# NinjaPCB_ver2-180115.net
KiCad netlist of a schematic drawn in EAGLE
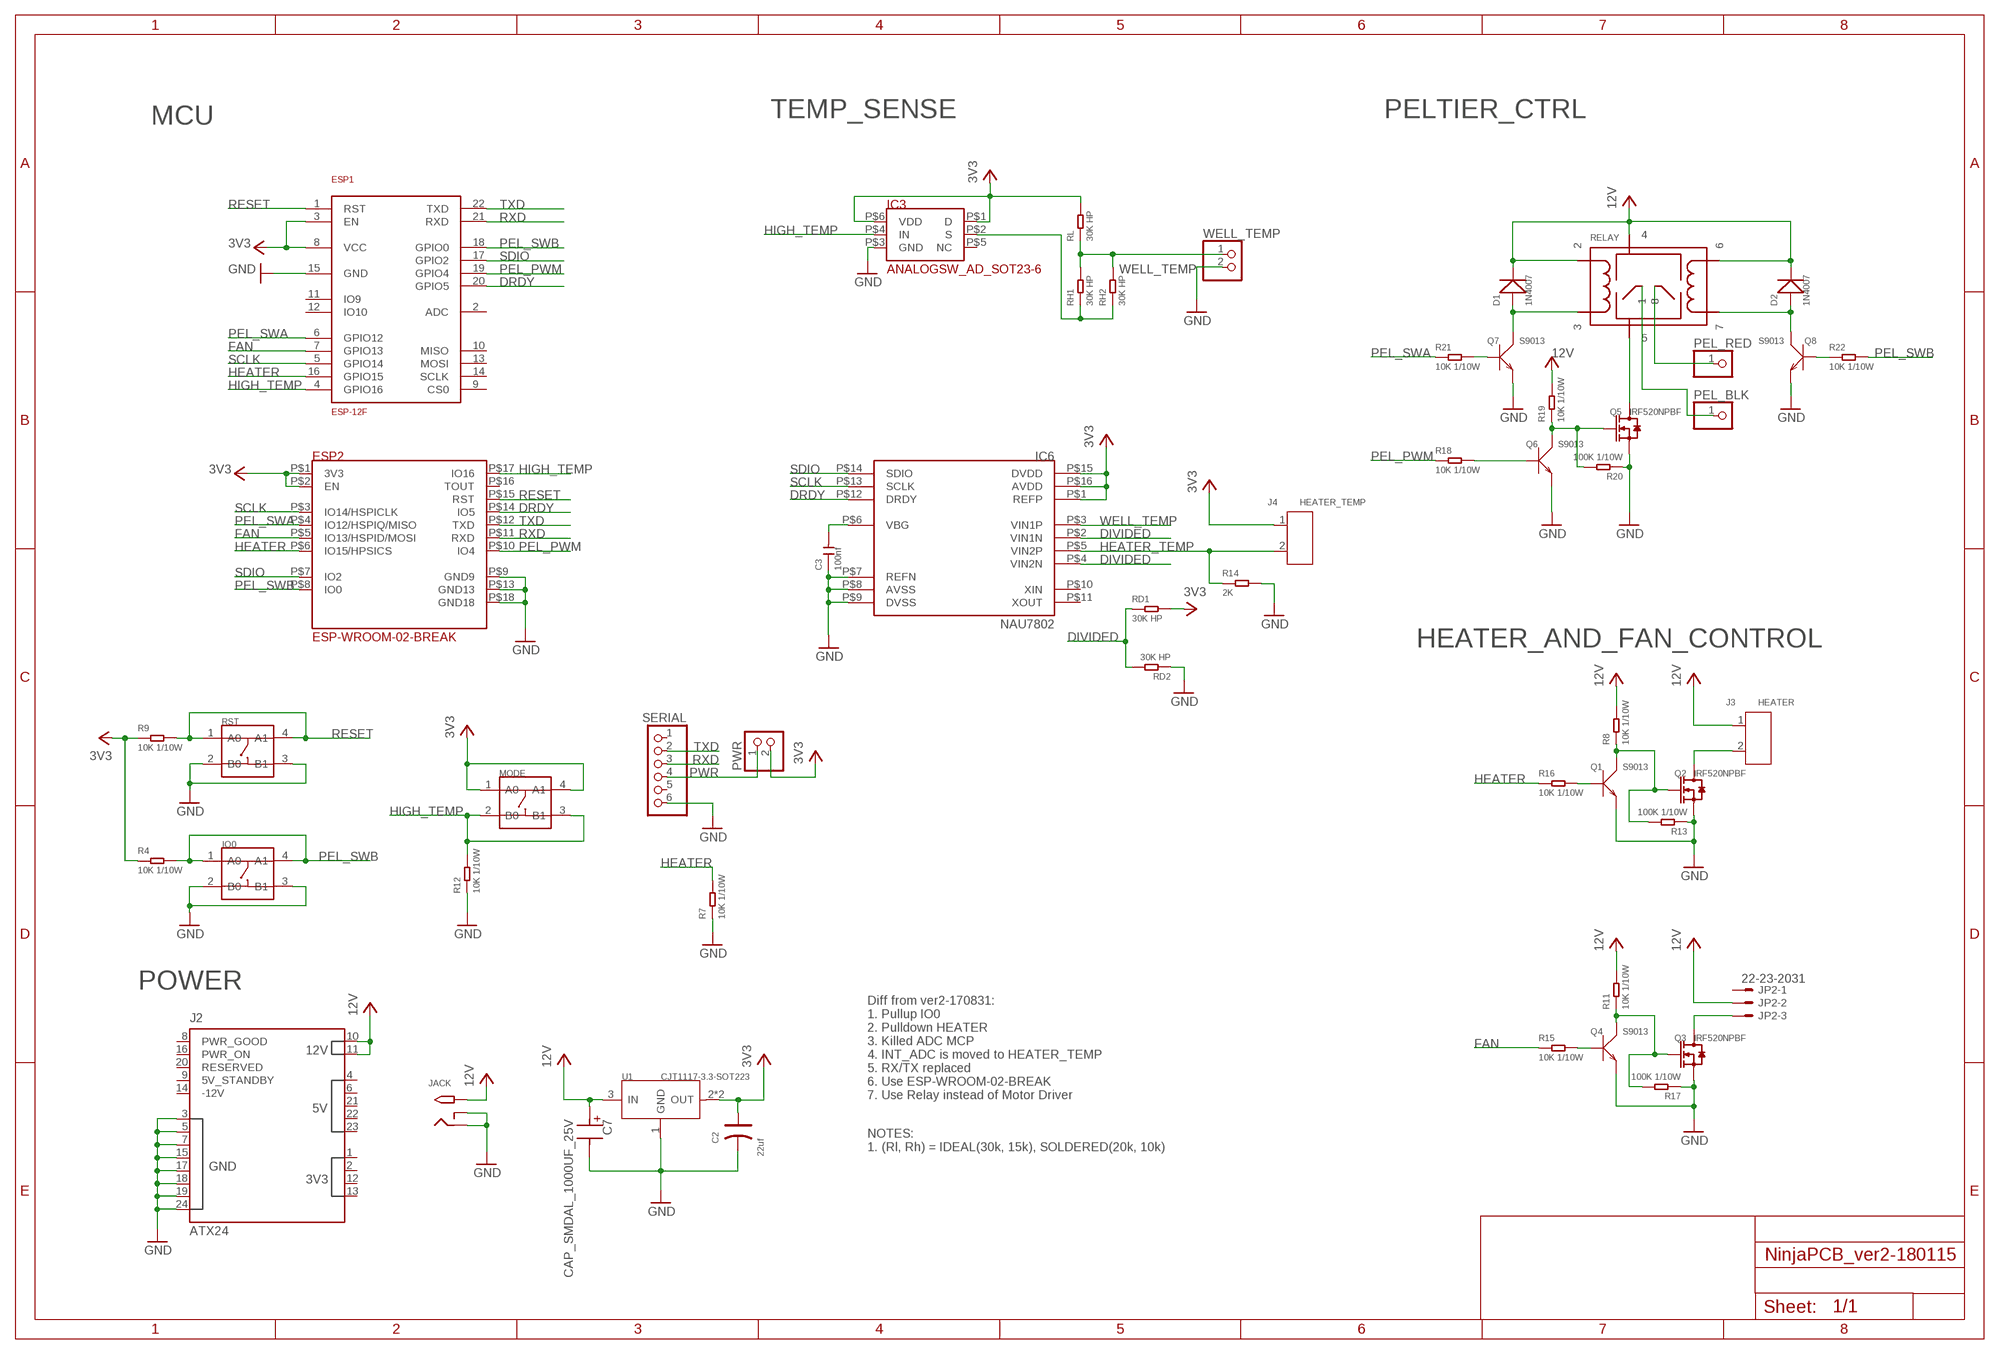
[diagram p0: schematic, sheet 1]

(export (version "E")
  (design (tool "Eeschema 10.0.6"))
  (components
    (comp (ref "C2")
      (value "22uf")
      (footprint "eagle-import:AVX-B")
      (fields (field (name "MPN") "TAJB226*016#NJ"))
      (libsource (lib "eagle-import") (part "TANTALUM-SMD-22UF-16V(AVX-B)"))
    )
    (comp (ref "C3")
      (value "100nf")
      (footprint "eagle-import:C0603")
      (fields (field (name "MPN") "CC0603KRX7R9BB104"))
      (libsource (lib "eagle-import") (part "CERAMIC-100NF-50V-10%-X7R(0603)"))
    )
    (comp (ref "C7")
      (value "CAP_SMDAL_1000UF_25V")
      (footprint "eagle-import:CAP_SMD_AL_D125")
      (libsource (lib "eagle-import") (part "CAP_SMDAL_1000UF_25V"))
    )
    (comp (ref "D1")
      (value "1N4007")
      (footprint "eagle-import:DO-214AC")
      (libsource (lib "eagle-import") (part "DIODE-GEN-PURPOSE-1KV-1A(DO-214AC)"))
    )
    (comp (ref "D2")
      (value "1N4007")
      (footprint "eagle-import:DO-214AC")
      (libsource (lib "eagle-import") (part "DIODE-GEN-PURPOSE-1KV-1A(DO-214AC)"))
    )
    (comp (ref "ESP1")
      (value "ESP-12F")
      (footprint "eagle-import:ESP-12F")
      (libsource (lib "eagle-import") (part "ESP-12F"))
    )
    (comp (ref "ESP2")
      (value "ESP-WROOM-02-BREAK")
      (footprint "eagle-import:ESP-WROOM-02-BREAK")
      (libsource (lib "eagle-import") (part "ESP-WROOM-02-BREAK"))
    )
    (comp (ref "IC3")
      (value "ANALOGSW_AD_SOT23-6")
      (footprint "eagle-import:SOT-23-6")
      (libsource (lib "eagle-import") (part "ANALOGSW_AD_SOT23-6"))
    )
    (comp (ref "IC6")
      (value "NAU7802")
      (footprint "eagle-import:SOP-16")
      (libsource (lib "eagle-import") (part "NAU7802"))
    )
    (comp (ref "IO0")
      (value "DIP-SWITCH-TACTILE-SPST-NO/TS-1109(4P-D6.0MM)'TS-1109'")
      (footprint "eagle-import:SW4-6.0X6.0X5.0MM")
      (libsource (lib "eagle-import") (part "DIP-SWITCH-TACTILE-SPST-NO/TS-1109(4P-D6.0MM)'TS-1109'"))
    )
    (comp (ref "J2")
      (value "ATX24")
      (footprint "eagle-import:ATX24")
      (libsource (lib "eagle-import") (part "ATX24"))
    )
    (comp (ref "J3")
      (value "HEATER")
      (footprint "eagle-import:H2-3.5-7.0X7.0MM")
      (libsource (lib "eagle-import") (part "SCREW-TERMINAL-GREEN(2P-3.5)"))
    )
    (comp (ref "J4")
      (value "HEATER_TEMP")
      (footprint "eagle-import:H2-3.5-7.0X7.0MM")
      (libsource (lib "eagle-import") (part "SCREW-TERMINAL-GREEN(2P-3.5)"))
    )
    (comp (ref "JACK")
      (value "2.1MMJACKTHM")
      (footprint "eagle-import:PJ-102A")
      (libsource (lib "eagle-import") (part "2.1MMJACKTHM"))
    )
    (comp (ref "JP2")
      (value "22-23-2031")
      (footprint "eagle-import:22-23-2031")
      (fields (field (name "MF") "MOLEX"))
      (libsource (lib "eagle-import") (part "22-23-2031"))
    )
    (comp (ref "MODE")
      (value "DIP-SWITCH-TACTILE-SPST-NO/TS-1109(4P-D6.0MM)'TS-1109'")
      (footprint "eagle-import:SW4-6.0X6.0X5.0MM")
      (libsource (lib "eagle-import") (part "DIP-SWITCH-TACTILE-SPST-NO/TS-1109(4P-D6.0MM)'TS-1109'"))
    )
    (comp (ref "PEL_BLK")
      (value "PINHD-1X1L")
      (footprint "eagle-import:1X01LONG")
      (libsource (lib "eagle-import") (part "PINHD-1X1L"))
    )
    (comp (ref "PEL_RED")
      (value "PINHD-1X1L")
      (footprint "eagle-import:1X01LONG")
      (libsource (lib "eagle-import") (part "PINHD-1X1L"))
    )
    (comp (ref "PWR")
      (value "PINHD-1X2")
      (footprint "eagle-import:1X02")
      (libsource (lib "eagle-import") (part "PINHD-1X2"))
    )
    (comp (ref "Q1")
      (value "S9013")
      (footprint "eagle-import:SOT-23")
      (libsource (lib "eagle-import") (part "SMD-TRANSISTORS-NPN-25V-500MA-S9013(SOT-23)"))
    )
    (comp (ref "Q2")
      (value "IRF520NPBF")
      (footprint "eagle-import:TO-220")
      (libsource (lib "eagle-import") (part "DIP-MOSFET-N-CH-100V-9.7A-IRF520NPBF(TO-220AB)CORRECT"))
    )
    (comp (ref "Q3")
      (value "IRF520NPBF")
      (footprint "eagle-import:TO-220")
      (libsource (lib "eagle-import") (part "DIP-MOSFET-N-CH-100V-9.7A-IRF520NPBF(TO-220AB)CORRECT"))
    )
    (comp (ref "Q4")
      (value "S9013")
      (footprint "eagle-import:SOT-23")
      (libsource (lib "eagle-import") (part "SMD-TRANSISTORS-NPN-25V-500MA-S9013(SOT-23)"))
    )
    (comp (ref "Q5")
      (value "IRF520NPBF")
      (footprint "eagle-import:TO-220")
      (libsource (lib "eagle-import") (part "DIP-MOSFET-N-CH-100V-9.7A-IRF520NPBF(TO-220AB)CORRECT"))
    )
    (comp (ref "Q6")
      (value "S9013")
      (footprint "eagle-import:SOT-23")
      (libsource (lib "eagle-import") (part "SMD-TRANSISTORS-NPN-25V-500MA-S9013(SOT-23)"))
    )
    (comp (ref "Q7")
      (value "S9013")
      (footprint "eagle-import:SOT-23")
      (libsource (lib "eagle-import") (part "SMD-TRANSISTORS-NPN-25V-500MA-S9013(SOT-23)"))
    )
    (comp (ref "Q8")
      (value "S9013")
      (footprint "eagle-import:SOT-23")
      (libsource (lib "eagle-import") (part "SMD-TRANSISTORS-NPN-25V-500MA-S9013(SOT-23)"))
    )
    (comp (ref "R4")
      (value "10K 1/10W")
      (footprint "eagle-import:R0603")
      (fields (field (name "MPN") "RC0603JR-0710KL"))
      (libsource (lib "eagle-import") (part "SMD-RES-10K-5%-1/10W(0603)"))
    )
    (comp (ref "R7")
      (value "10K 1/10W")
      (footprint "eagle-import:R0603")
      (fields (field (name "MPN") "RC0603JR-0710KL"))
      (libsource (lib "eagle-import") (part "SMD-RES-10K-5%-1/10W(0603)"))
    )
    (comp (ref "R8")
      (value "10K 1/10W")
      (footprint "eagle-import:R0603")
      (fields (field (name "MPN") "RC0603JR-0710KL"))
      (libsource (lib "eagle-import") (part "SMD-RES-10K-5%-1/10W(0603)"))
    )
    (comp (ref "R9")
      (value "10K 1/10W")
      (footprint "eagle-import:R0603")
      (fields (field (name "MPN") "RC0603JR-0710KL"))
      (libsource (lib "eagle-import") (part "SMD-RES-10K-5%-1/10W(0603)"))
    )
    (comp (ref "R11")
      (value "10K 1/10W")
      (footprint "eagle-import:R0603")
      (fields (field (name "MPN") "RC0603JR-0710KL"))
      (libsource (lib "eagle-import") (part "SMD-RES-10K-5%-1/10W(0603)"))
    )
    (comp (ref "R12")
      (value "10K 1/10W")
      (footprint "eagle-import:R0603")
      (fields (field (name "MPN") "RC0603JR-0710KL"))
      (libsource (lib "eagle-import") (part "SMD-RES-10K-5%-1/10W(0603)"))
    )
    (comp (ref "R13")
      (value "100K 1/10W")
      (footprint "eagle-import:R0603")
      (fields (field (name "MPN") "RC0603JR-07100KL"))
      (libsource (lib "eagle-import") (part "SMD-RES-100K-5%-1/10W(0603)"))
    )
    (comp (ref "R14")
      (value "2K")
      (footprint "eagle-import:R0603")
      (fields (field (name "MPN") "RC0603FR-072KL"))
      (libsource (lib "eagle-import") (part "SMD-RES-2K-1%-1/10W(0603)"))
    )
    (comp (ref "R15")
      (value "10K 1/10W")
      (footprint "eagle-import:R0603")
      (fields (field (name "MPN") "RC0603JR-0710KL"))
      (libsource (lib "eagle-import") (part "SMD-RES-10K-5%-1/10W(0603)"))
    )
    (comp (ref "R16")
      (value "10K 1/10W")
      (footprint "eagle-import:R0603")
      (fields (field (name "MPN") "RC0603JR-0710KL"))
      (libsource (lib "eagle-import") (part "SMD-RES-10K-5%-1/10W(0603)"))
    )
    (comp (ref "R17")
      (value "100K 1/10W")
      (footprint "eagle-import:R0603")
      (fields (field (name "MPN") "RC0603JR-07100KL"))
      (libsource (lib "eagle-import") (part "SMD-RES-100K-5%-1/10W(0603)"))
    )
    (comp (ref "R18")
      (value "10K 1/10W")
      (footprint "eagle-import:R0603")
      (fields (field (name "MPN") "RC0603JR-0710KL"))
      (libsource (lib "eagle-import") (part "SMD-RES-10K-5%-1/10W(0603)"))
    )
    (comp (ref "R19")
      (value "10K 1/10W")
      (footprint "eagle-import:R0603")
      (fields (field (name "MPN") "RC0603JR-0710KL"))
      (libsource (lib "eagle-import") (part "SMD-RES-10K-5%-1/10W(0603)"))
    )
    (comp (ref "R20")
      (value "100K 1/10W")
      (footprint "eagle-import:R0603")
      (fields (field (name "MPN") "RC0603JR-07100KL"))
      (libsource (lib "eagle-import") (part "SMD-RES-100K-5%-1/10W(0603)"))
    )
    (comp (ref "R21")
      (value "10K 1/10W")
      (footprint "eagle-import:R0603")
      (fields (field (name "MPN") "RC0603JR-0710KL"))
      (libsource (lib "eagle-import") (part "SMD-RES-10K-5%-1/10W(0603)"))
    )
    (comp (ref "R22")
      (value "10K 1/10W")
      (footprint "eagle-import:R0603")
      (fields (field (name "MPN") "RC0603JR-0710KL"))
      (libsource (lib "eagle-import") (part "SMD-RES-10K-5%-1/10W(0603)"))
    )
    (comp (ref "RD1")
      (value "30K HP")
      (footprint "eagle-import:R0603")
      (libsource (lib "eagle-import") (part "R0603"))
    )
    (comp (ref "RD2")
      (value "30K HP")
      (footprint "eagle-import:R0603")
      (libsource (lib "eagle-import") (part "R0603"))
    )
    (comp (ref "RELAY")
      (value "NEC-RELAY2ET2")
      (footprint "eagle-import:NEC-ET2-N8")
      (libsource (lib "eagle-import") (part "NEC-RELAY2ET2"))
    )
    (comp (ref "RH1")
      (value "30K HP")
      (footprint "eagle-import:R0603")
      (libsource (lib "eagle-import") (part "R0603"))
    )
    (comp (ref "RH2")
      (value "30K HP")
      (footprint "eagle-import:R0603")
      (libsource (lib "eagle-import") (part "R0603"))
    )
    (comp (ref "RL")
      (value "30K HP")
      (footprint "eagle-import:R0603")
      (libsource (lib "eagle-import") (part "R0603"))
    )
    (comp (ref "RST")
      (value "DIP-SWITCH-TACTILE-SPST-NO/TS-1109(4P-D6.0MM)'TS-1109'")
      (footprint "eagle-import:SW4-6.0X6.0X5.0MM")
      (libsource (lib "eagle-import") (part "DIP-SWITCH-TACTILE-SPST-NO/TS-1109(4P-D6.0MM)'TS-1109'"))
    )
    (comp (ref "SERIAL")
      (value "PINHD-1X6")
      (footprint "eagle-import:1X06")
      (libsource (lib "eagle-import") (part "PINHD-1X6"))
    )
    (comp (ref "U1")
      (value "CJT1117-3.3-SOT223")
      (footprint "eagle-import:SOT-223")
      (fields (field (name "MPN") "CJT1117-3.3"))
      (libsource (lib "eagle-import") (part "PMIC-CJT1117-3.3(SOT223)"))
    )
    (comp (ref "WELL_TEMP")
      (value "PINHD-1X2")
      (footprint "eagle-import:1X02")
      (libsource (lib "eagle-import") (part "PINHD-1X2"))
    )
  )
  (nets
    (net (code "1") (name "/DIVIDED") (class "Default")
      (node (ref "IC6") (pin "P$2") (pinfunction "VIN1N_P$2") (pintype "bidirectional"))
      (node (ref "IC6") (pin "P$4") (pinfunction "VIN2N_P$4") (pintype "bidirectional"))
      (node (ref "RD1") (pin "1") (pinfunction "1_1") (pintype "passive"))
      (node (ref "RD2") (pin "2") (pinfunction "2_2") (pintype "passive"))
    )
    (net (code "2") (name "/DRDY") (class "Default")
      (node (ref "ESP1") (pin "20") (pinfunction "GPIO5_20") (pintype "bidirectional"))
      (node (ref "ESP2") (pin "P$14") (pinfunction "IO5_P$14") (pintype "bidirectional"))
      (node (ref "IC6") (pin "P$12") (pinfunction "DRDY_P$12") (pintype "bidirectional"))
    )
    (net (code "3") (name "/FAN") (class "Default")
      (node (ref "ESP1") (pin "7") (pinfunction "GPIO13_7") (pintype "bidirectional"))
      (node (ref "ESP2") (pin "P$5") (pinfunction "IO13/HSPID/MOSI_P$5") (pintype "bidirectional"))
      (node (ref "R15") (pin "1") (pinfunction "1_1") (pintype "passive"))
    )
    (net (code "4") (name "/HEATER") (class "Default")
      (node (ref "ESP1") (pin "16") (pinfunction "GPIO15_16") (pintype "bidirectional"))
      (node (ref "ESP2") (pin "P$6") (pinfunction "IO15/HPSICS_P$6") (pintype "bidirectional"))
      (node (ref "R16") (pin "1") (pinfunction "1_1") (pintype "passive"))
      (node (ref "R7") (pin "2") (pinfunction "2_2") (pintype "passive"))
    )
    (net (code "5") (name "/HEATER_TEMP") (class "Default")
      (node (ref "IC6") (pin "P$5") (pinfunction "VIN2P_P$5") (pintype "bidirectional"))
      (node (ref "J4") (pin "2") (pinfunction "2_2") (pintype "bidirectional"))
      (node (ref "R14") (pin "1") (pinfunction "1_1") (pintype "passive"))
    )
    (net (code "6") (name "/HIGH_TEMP") (class "Default")
      (node (ref "ESP1") (pin "4") (pinfunction "GPIO16_4") (pintype "bidirectional"))
      (node (ref "ESP2") (pin "P$17") (pinfunction "IO16_P$17") (pintype "bidirectional"))
      (node (ref "IC3") (pin "P$4") (pinfunction "IN_P$4") (pintype "bidirectional"))
      (node (ref "MODE") (pin "2") (pinfunction "B0_2") (pintype "bidirectional"))
      (node (ref "MODE") (pin "3") (pinfunction "B1_3") (pintype "bidirectional"))
      (node (ref "R12") (pin "2") (pinfunction "2_2") (pintype "passive"))
    )
    (net (code "7") (name "/PEL_PWM") (class "Default")
      (node (ref "ESP1") (pin "19") (pinfunction "GPIO4_19") (pintype "bidirectional"))
      (node (ref "ESP2") (pin "P$10") (pinfunction "IO4_P$10") (pintype "bidirectional"))
      (node (ref "R18") (pin "1") (pinfunction "1_1") (pintype "passive"))
    )
    (net (code "8") (name "/PEL_SWA") (class "Default")
      (node (ref "ESP1") (pin "6") (pinfunction "GPIO12_6") (pintype "bidirectional"))
      (node (ref "ESP2") (pin "P$4") (pinfunction "IO12/HSPIQ/MISO_P$4") (pintype "bidirectional"))
      (node (ref "R21") (pin "1") (pinfunction "1_1") (pintype "passive"))
    )
    (net (code "9") (name "/PEL_SWB") (class "Default")
      (node (ref "ESP1") (pin "18") (pinfunction "GPIO0_18") (pintype "bidirectional"))
      (node (ref "ESP2") (pin "P$8") (pinfunction "IO0_P$8") (pintype "bidirectional"))
      (node (ref "IO0") (pin "1") (pinfunction "A0_1") (pintype "bidirectional"))
      (node (ref "IO0") (pin "4") (pinfunction "A1_4") (pintype "bidirectional"))
      (node (ref "R22") (pin "2") (pinfunction "2_2") (pintype "passive"))
      (node (ref "R4") (pin "2") (pinfunction "2_2") (pintype "passive"))
    )
    (net (code "10") (name "/PWR") (class "Default")
      (node (ref "PWR") (pin "1") (pinfunction "1_1") (pintype "passive"))
      (node (ref "SERIAL") (pin "4") (pinfunction "4_4") (pintype "passive"))
    )
    (net (code "11") (name "/RESET") (class "Default")
      (node (ref "ESP1") (pin "1") (pinfunction "RST_1") (pintype "bidirectional"))
      (node (ref "ESP2") (pin "P$15") (pinfunction "RST_P$15") (pintype "bidirectional"))
      (node (ref "R9") (pin "2") (pinfunction "2_2") (pintype "passive"))
      (node (ref "RST") (pin "1") (pinfunction "A0_1") (pintype "bidirectional"))
      (node (ref "RST") (pin "4") (pinfunction "A1_4") (pintype "bidirectional"))
    )
    (net (code "12") (name "/RXD") (class "Default")
      (node (ref "ESP1") (pin "21") (pinfunction "RXD_21") (pintype "bidirectional"))
      (node (ref "ESP2") (pin "P$11") (pinfunction "RXD_P$11") (pintype "bidirectional"))
      (node (ref "SERIAL") (pin "3") (pinfunction "3_3") (pintype "passive"))
    )
    (net (code "13") (name "/SCLK") (class "Default")
      (node (ref "ESP1") (pin "5") (pinfunction "GPIO14_5") (pintype "bidirectional"))
      (node (ref "ESP2") (pin "P$3") (pinfunction "IO14/HSPICLK_P$3") (pintype "bidirectional"))
      (node (ref "IC6") (pin "P$13") (pinfunction "SCLK_P$13") (pintype "bidirectional"))
    )
    (net (code "14") (name "/SDIO") (class "Default")
      (node (ref "ESP1") (pin "17") (pinfunction "GPIO2_17") (pintype "bidirectional"))
      (node (ref "ESP2") (pin "P$7") (pinfunction "IO2_P$7") (pintype "bidirectional"))
      (node (ref "IC6") (pin "P$14") (pinfunction "SDIO_P$14") (pintype "bidirectional"))
    )
    (net (code "15") (name "/TXD") (class "Default")
      (node (ref "ESP1") (pin "22") (pinfunction "TXD_22") (pintype "bidirectional"))
      (node (ref "ESP2") (pin "P$12") (pinfunction "TXD_P$12") (pintype "bidirectional"))
      (node (ref "SERIAL") (pin "2") (pinfunction "2_2") (pintype "passive"))
    )
    (net (code "16") (name "/WELL_TEMP") (class "Default")
      (node (ref "IC6") (pin "P$3") (pinfunction "VIN1P_P$3") (pintype "bidirectional"))
      (node (ref "RH1") (pin "2") (pinfunction "2_2") (pintype "passive"))
      (node (ref "RH2") (pin "2") (pinfunction "2_2") (pintype "passive"))
      (node (ref "RL") (pin "1") (pinfunction "1_1") (pintype "passive"))
      (node (ref "WELL_TEMP") (pin "1") (pinfunction "1_1") (pintype "passive"))
    )
    (net (code "17") (name "3V3") (class "Default")
      (node (ref "C2") (pin "+") (pinfunction "+_+") (pintype "passive"))
      (node (ref "ESP1") (pin "3") (pinfunction "EN_3") (pintype "bidirectional"))
      (node (ref "ESP1") (pin "8") (pinfunction "VCC_8") (pintype "bidirectional"))
      (node (ref "ESP2") (pin "P$1") (pinfunction "3V3_P$1") (pintype "bidirectional"))
      (node (ref "ESP2") (pin "P$2") (pinfunction "EN_P$2") (pintype "bidirectional"))
      (node (ref "IC3") (pin "P$1") (pinfunction "D_P$1") (pintype "bidirectional"))
      (node (ref "IC3") (pin "P$6") (pinfunction "VDD_P$6") (pintype "bidirectional"))
      (node (ref "IC6") (pin "P$1") (pinfunction "REFP_P$1") (pintype "bidirectional"))
      (node (ref "IC6") (pin "P$15") (pinfunction "DVDD_P$15") (pintype "bidirectional"))
      (node (ref "IC6") (pin "P$16") (pinfunction "AVDD_P$16") (pintype "bidirectional"))
      (node (ref "J4") (pin "1") (pinfunction "1_1") (pintype "bidirectional"))
      (node (ref "MODE") (pin "1") (pinfunction "A0_1") (pintype "bidirectional"))
      (node (ref "MODE") (pin "4") (pinfunction "A1_4") (pintype "bidirectional"))
      (node (ref "PWR") (pin "2") (pinfunction "2_2") (pintype "passive"))
      (node (ref "R4") (pin "1") (pinfunction "1_1") (pintype "passive"))
      (node (ref "R9") (pin "1") (pinfunction "1_1") (pintype "passive"))
      (node (ref "RD1") (pin "2") (pinfunction "2_2") (pintype "passive"))
      (node (ref "RL") (pin "2") (pinfunction "2_2") (pintype "passive"))
      (node (ref "U1") (pin "2") (pinfunction "OUT_2") (pintype "bidirectional"))
      (node (ref "U1") (pin "TER") (pinfunction "OUT_TER") (pintype "bidirectional"))
    )
    (net (code "18") (name "12V") (class "Default")
      (node (ref "C7") (pin "P$P") (pinfunction "P$P_P$P") (pintype "passive"))
      (node (ref "D1") (pin "2") (pinfunction "-_2") (pintype "passive"))
      (node (ref "D2") (pin "2") (pinfunction "-_2") (pintype "passive"))
      (node (ref "J2") (pin "10") (pinfunction "12V_10_10") (pintype "bidirectional"))
      (node (ref "J2") (pin "11") (pinfunction "12V_11_11") (pintype "bidirectional"))
      (node (ref "J3") (pin "1") (pinfunction "1_1") (pintype "bidirectional"))
      (node (ref "JACK") (pin "TIP") (pinfunction "TIP_TIP") (pintype "bidirectional"))
      (node (ref "JP2") (pin "2") (pinfunction "S_2") (pintype "passive"))
      (node (ref "R11") (pin "2") (pinfunction "2_2") (pintype "passive"))
      (node (ref "R19") (pin "2") (pinfunction "2_2") (pintype "passive"))
      (node (ref "R8") (pin "2") (pinfunction "2_2") (pintype "passive"))
      (node (ref "RELAY") (pin "P$2") (pinfunction "2_P$2") (pintype "bidirectional"))
      (node (ref "RELAY") (pin "P$4") (pinfunction "4_P$4") (pintype "bidirectional"))
      (node (ref "RELAY") (pin "P$6") (pinfunction "6_P$6") (pintype "bidirectional"))
      (node (ref "U1") (pin "3") (pinfunction "IN_3") (pintype "bidirectional"))
    )
    (net (code "19") (name "GND") (class "Default")
      (node (ref "C2") (pin "-") (pinfunction "-_-") (pintype "passive"))
      (node (ref "C3") (pin "1") (pinfunction "1_1") (pintype "passive"))
      (node (ref "C7") (pin "P$M") (pinfunction "P$M_P$M") (pintype "passive"))
      (node (ref "ESP1") (pin "15") (pinfunction "GND_15") (pintype "bidirectional"))
      (node (ref "ESP2") (pin "P$13") (pinfunction "GND13_P$13") (pintype "bidirectional"))
      (node (ref "ESP2") (pin "P$18") (pinfunction "GND18_P$18") (pintype "bidirectional"))
      (node (ref "ESP2") (pin "P$9") (pinfunction "GND9_P$9") (pintype "bidirectional"))
      (node (ref "IC3") (pin "P$3") (pinfunction "GND_P$3") (pintype "bidirectional"))
      (node (ref "IC6") (pin "P$7") (pinfunction "REFN_P$7") (pintype "bidirectional"))
      (node (ref "IC6") (pin "P$8") (pinfunction "AVSS_P$8") (pintype "bidirectional"))
      (node (ref "IC6") (pin "P$9") (pinfunction "DVSS_P$9") (pintype "bidirectional"))
      (node (ref "IO0") (pin "2") (pinfunction "B0_2") (pintype "bidirectional"))
      (node (ref "IO0") (pin "3") (pinfunction "B1_3") (pintype "bidirectional"))
      (node (ref "J2") (pin "15") (pinfunction "GND15_15") (pintype "bidirectional"))
      (node (ref "J2") (pin "17") (pinfunction "GND17_17") (pintype "bidirectional"))
      (node (ref "J2") (pin "18") (pinfunction "GND18_18") (pintype "bidirectional"))
      (node (ref "J2") (pin "19") (pinfunction "GND19_19") (pintype "bidirectional"))
      (node (ref "J2") (pin "24") (pinfunction "GND24_24") (pintype "bidirectional"))
      (node (ref "J2") (pin "3") (pinfunction "GND3_3") (pintype "bidirectional"))
      (node (ref "J2") (pin "5") (pinfunction "GND5_5") (pintype "bidirectional"))
      (node (ref "J2") (pin "7") (pinfunction "GND7_7") (pintype "bidirectional"))
      (node (ref "JACK") (pin "RING") (pinfunction "RING_RING") (pintype "bidirectional"))
      (node (ref "JACK") (pin "RING_SW") (pinfunction "RING_SW_RING_SW") (pintype "bidirectional"))
      (node (ref "Q1") (pin "2") (pinfunction "E_2") (pintype "passive"))
      (node (ref "Q2") (pin "3") (pinfunction "S_3") (pintype "passive"))
      (node (ref "Q3") (pin "3") (pinfunction "S_3") (pintype "passive"))
      (node (ref "Q4") (pin "2") (pinfunction "E_2") (pintype "passive"))
      (node (ref "Q5") (pin "3") (pinfunction "S_3") (pintype "passive"))
      (node (ref "Q6") (pin "2") (pinfunction "E_2") (pintype "passive"))
      (node (ref "Q7") (pin "2") (pinfunction "E_2") (pintype "passive"))
      (node (ref "Q8") (pin "2") (pinfunction "E_2") (pintype "passive"))
      (node (ref "R12") (pin "1") (pinfunction "1_1") (pintype "passive"))
      (node (ref "R13") (pin "1") (pinfunction "1_1") (pintype "passive"))
      (node (ref "R14") (pin "2") (pinfunction "2_2") (pintype "passive"))
      (node (ref "R17") (pin "1") (pinfunction "1_1") (pintype "passive"))
      (node (ref "R20") (pin "1") (pinfunction "1_1") (pintype "passive"))
      (node (ref "R7") (pin "1") (pinfunction "1_1") (pintype "passive"))
      (node (ref "RD2") (pin "1") (pinfunction "1_1") (pintype "passive"))
      (node (ref "RST") (pin "2") (pinfunction "B0_2") (pintype "bidirectional"))
      (node (ref "RST") (pin "3") (pinfunction "B1_3") (pintype "bidirectional"))
      (node (ref "SERIAL") (pin "6") (pinfunction "6_6") (pintype "passive"))
      (node (ref "U1") (pin "1") (pinfunction "GND_1") (pintype "bidirectional"))
      (node (ref "WELL_TEMP") (pin "2") (pinfunction "2_2") (pintype "passive"))
    )
    (net (code "20") (name "Net-(D1-+)") (class "Default")
      (node (ref "D1") (pin "1") (pinfunction "+_1") (pintype "passive"))
      (node (ref "Q7") (pin "3") (pinfunction "C_3") (pintype "passive"))
      (node (ref "RELAY") (pin "P$3") (pinfunction "3_P$3") (pintype "bidirectional"))
    )
    (net (code "21") (name "Net-(D2-+)") (class "Default")
      (node (ref "D2") (pin "1") (pinfunction "+_1") (pintype "passive"))
      (node (ref "Q8") (pin "3") (pinfunction "C_3") (pintype "passive"))
      (node (ref "RELAY") (pin "P$7") (pinfunction "7_P$7") (pintype "bidirectional"))
    )
    (net (code "22") (name "Net-(IC3-S)") (class "Default")
      (node (ref "IC3") (pin "P$2") (pinfunction "S_P$2") (pintype "bidirectional"))
      (node (ref "RH1") (pin "1") (pinfunction "1_1") (pintype "passive"))
      (node (ref "RH2") (pin "1") (pinfunction "1_1") (pintype "passive"))
    )
    (net (code "23") (name "Net-(IC6-VBG)") (class "Default")
      (node (ref "C3") (pin "2") (pinfunction "2_2") (pintype "passive"))
      (node (ref "IC6") (pin "P$6") (pinfunction "VBG_P$6") (pintype "bidirectional"))
    )
    (net (code "24") (name "Net-(J3-Pad2)") (class "Default")
      (node (ref "J3") (pin "2") (pinfunction "2_2") (pintype "bidirectional"))
      (node (ref "Q2") (pin "2") (pinfunction "D_2") (pintype "passive"))
      (node (ref "Q2") (pin "HEAT") (pinfunction "D_HEAT") (pintype "passive"))
    )
    (net (code "25") (name "Net-(JP2C-S)") (class "Default")
      (node (ref "JP2") (pin "3") (pinfunction "S_3") (pintype "passive"))
      (node (ref "Q3") (pin "2") (pinfunction "D_2") (pintype "passive"))
      (node (ref "Q3") (pin "HEAT") (pinfunction "D_HEAT") (pintype "passive"))
    )
    (net (code "26") (name "Net-(Q1-B)") (class "Default")
      (node (ref "Q1") (pin "1") (pinfunction "B_1") (pintype "passive"))
      (node (ref "R16") (pin "2") (pinfunction "2_2") (pintype "passive"))
    )
    (net (code "27") (name "Net-(Q1-C)") (class "Default")
      (node (ref "Q1") (pin "3") (pinfunction "C_3") (pintype "passive"))
      (node (ref "Q2") (pin "1") (pinfunction "G_1") (pintype "passive"))
      (node (ref "R13") (pin "2") (pinfunction "2_2") (pintype "passive"))
      (node (ref "R8") (pin "1") (pinfunction "1_1") (pintype "passive"))
    )
    (net (code "28") (name "Net-(Q3-G)") (class "Default")
      (node (ref "Q3") (pin "1") (pinfunction "G_1") (pintype "passive"))
      (node (ref "Q4") (pin "3") (pinfunction "C_3") (pintype "passive"))
      (node (ref "R11") (pin "1") (pinfunction "1_1") (pintype "passive"))
      (node (ref "R17") (pin "2") (pinfunction "2_2") (pintype "passive"))
    )
    (net (code "29") (name "Net-(Q4-B)") (class "Default")
      (node (ref "Q4") (pin "1") (pinfunction "B_1") (pintype "passive"))
      (node (ref "R15") (pin "2") (pinfunction "2_2") (pintype "passive"))
    )
    (net (code "30") (name "Net-(Q5-G)") (class "Default")
      (node (ref "Q5") (pin "1") (pinfunction "G_1") (pintype "passive"))
      (node (ref "Q6") (pin "3") (pinfunction "C_3") (pintype "passive"))
      (node (ref "R19") (pin "1") (pinfunction "1_1") (pintype "passive"))
      (node (ref "R20") (pin "2") (pinfunction "2_2") (pintype "passive"))
    )
    (net (code "31") (name "Net-(Q6-B)") (class "Default")
      (node (ref "Q6") (pin "1") (pinfunction "B_1") (pintype "passive"))
      (node (ref "R18") (pin "2") (pinfunction "2_2") (pintype "passive"))
    )
    (net (code "32") (name "Net-(Q7-B)") (class "Default")
      (node (ref "Q7") (pin "1") (pinfunction "B_1") (pintype "passive"))
      (node (ref "R21") (pin "2") (pinfunction "2_2") (pintype "passive"))
    )
    (net (code "33") (name "Net-(Q8-B)") (class "Default")
      (node (ref "Q8") (pin "1") (pinfunction "B_1") (pintype "passive"))
      (node (ref "R22") (pin "1") (pinfunction "1_1") (pintype "passive"))
    )
    (net (code "34") (name "Net-(RELAY-1)") (class "Default")
      (node (ref "PEL_BLK") (pin "1") (pinfunction "1_1") (pintype "passive"))
      (node (ref "RELAY") (pin "P$1") (pinfunction "1_P$1") (pintype "bidirectional"))
    )
    (net (code "35") (name "Net-(RELAY-5)") (class "Default")
      (node (ref "Q5") (pin "2") (pinfunction "D_2") (pintype "passive"))
      (node (ref "Q5") (pin "HEAT") (pinfunction "D_HEAT") (pintype "passive"))
      (node (ref "RELAY") (pin "P$5") (pinfunction "5_P$5") (pintype "bidirectional"))
    )
    (net (code "36") (name "Net-(RELAY-8)") (class "Default")
      (node (ref "PEL_RED") (pin "1") (pinfunction "1_1") (pintype "passive"))
      (node (ref "RELAY") (pin "P$8") (pinfunction "8_P$8") (pintype "bidirectional"))
    )
    (net (code "37") (name "unconnected-(ESP1-ADC-Pad2)") (class "Default")
      (node (ref "ESP1") (pin "2") (pinfunction "ADC_2") (pintype "bidirectional"))
    )
    (net (code "38") (name "unconnected-(ESP1-CS0-Pad9)") (class "Default")
      (node (ref "ESP1") (pin "9") (pinfunction "CS0_9") (pintype "bidirectional"))
    )
    (net (code "39") (name "unconnected-(ESP1-IO9-Pad11)") (class "Default")
      (node (ref "ESP1") (pin "11") (pinfunction "IO9_11") (pintype "bidirectional"))
    )
    (net (code "40") (name "unconnected-(ESP1-IO10-Pad12)") (class "Default")
      (node (ref "ESP1") (pin "12") (pinfunction "IO10_12") (pintype "bidirectional"))
    )
    (net (code "41") (name "unconnected-(ESP1-MISO-Pad10)") (class "Default")
      (node (ref "ESP1") (pin "10") (pinfunction "MISO_10") (pintype "bidirectional"))
    )
    (net (code "42") (name "unconnected-(ESP1-MOSI-Pad13)") (class "Default")
      (node (ref "ESP1") (pin "13") (pinfunction "MOSI_13") (pintype "bidirectional"))
    )
    (net (code "43") (name "unconnected-(ESP1-SCLK-Pad14)") (class "Default")
      (node (ref "ESP1") (pin "14") (pinfunction "SCLK_14") (pintype "bidirectional"))
    )
    (net (code "44") (name "unconnected-(ESP2-TOUT-PadP$16)") (class "Default")
      (node (ref "ESP2") (pin "P$16") (pinfunction "TOUT_P$16") (pintype "bidirectional"))
    )
    (net (code "45") (name "unconnected-(IC3-NC-PadP$5)") (class "Default")
      (node (ref "IC3") (pin "P$5") (pinfunction "NC_P$5") (pintype "bidirectional"))
    )
    (net (code "46") (name "unconnected-(IC6-XIN-PadP$10)") (class "Default")
      (node (ref "IC6") (pin "P$10") (pinfunction "XIN_P$10") (pintype "bidirectional"))
    )
    (net (code "47") (name "unconnected-(IC6-XOUT-PadP$11)") (class "Default")
      (node (ref "IC6") (pin "P$11") (pinfunction "XOUT_P$11") (pintype "bidirectional"))
    )
    (net (code "48") (name "unconnected-(J2--12V-Pad14)") (class "Default")
      (node (ref "J2") (pin "14") (pinfunction "-12V_14") (pintype "bidirectional"))
    )
    (net (code "49") (name "unconnected-(J2-3V3_1-Pad1)") (class "Default")
      (node (ref "J2") (pin "1") (pinfunction "3V3_1_1") (pintype "bidirectional"))
    )
    (net (code "50") (name "unconnected-(J2-3V3_2-Pad2)") (class "Default")
      (node (ref "J2") (pin "2") (pinfunction "3V3_2_2") (pintype "bidirectional"))
    )
    (net (code "51") (name "unconnected-(J2-3V3_12-Pad12)") (class "Default")
      (node (ref "J2") (pin "12") (pinfunction "3V3_12_12") (pintype "bidirectional"))
    )
    (net (code "52") (name "unconnected-(J2-3V3_13-Pad13)") (class "Default")
      (node (ref "J2") (pin "13") (pinfunction "3V3_13_13") (pintype "bidirectional"))
    )
    (net (code "53") (name "unconnected-(J2-5V_4-Pad4)") (class "Default")
      (node (ref "J2") (pin "4") (pinfunction "5V_4_4") (pintype "bidirectional"))
    )
    (net (code "54") (name "unconnected-(J2-5V_6-Pad6)") (class "Default")
      (node (ref "J2") (pin "6") (pinfunction "5V_6_6") (pintype "bidirectional"))
    )
    (net (code "55") (name "unconnected-(J2-5V_21-Pad21)") (class "Default")
      (node (ref "J2") (pin "21") (pinfunction "5V_21_21") (pintype "bidirectional"))
    )
    (net (code "56") (name "unconnected-(J2-5V_22-Pad22)") (class "Default")
      (node (ref "J2") (pin "22") (pinfunction "5V_22_22") (pintype "bidirectional"))
    )
    (net (code "57") (name "unconnected-(J2-5V_23-Pad23)") (class "Default")
      (node (ref "J2") (pin "23") (pinfunction "5V_23_23") (pintype "bidirectional"))
    )
    (net (code "58") (name "unconnected-(J2-5V_STANDBY-Pad9)") (class "Default")
      (node (ref "J2") (pin "9") (pinfunction "5V_STANDBY_9") (pintype "bidirectional"))
    )
    (net (code "59") (name "unconnected-(J2-PWR_GOOD-Pad8)") (class "Default")
      (node (ref "J2") (pin "8") (pinfunction "PWR_GOOD_8") (pintype "bidirectional"))
    )
    (net (code "60") (name "unconnected-(J2-PWR_ON-Pad16)") (class "Default")
      (node (ref "J2") (pin "16") (pinfunction "PWR_ON_16") (pintype "bidirectional"))
    )
    (net (code "61") (name "unconnected-(J2-RESERVED-Pad20)") (class "Default")
      (node (ref "J2") (pin "20") (pinfunction "RESERVED_20") (pintype "bidirectional"))
    )
    (net (code "62") (name "unconnected-(JP2A-S-Pad1)") (class "Default")
      (node (ref "JP2") (pin "1") (pinfunction "S_1") (pintype "passive"))
    )
    (net (code "63") (name "unconnected-(SERIAL-Pad1)") (class "Default")
      (node (ref "SERIAL") (pin "1") (pinfunction "1_1") (pintype "passive"))
    )
    (net (code "64") (name "unconnected-(SERIAL-Pad5)") (class "Default")
      (node (ref "SERIAL") (pin "5") (pinfunction "5_5") (pintype "passive"))
    )
  )
)
